# main.net
KiCad netlist of a schematic drawn in EAGLE
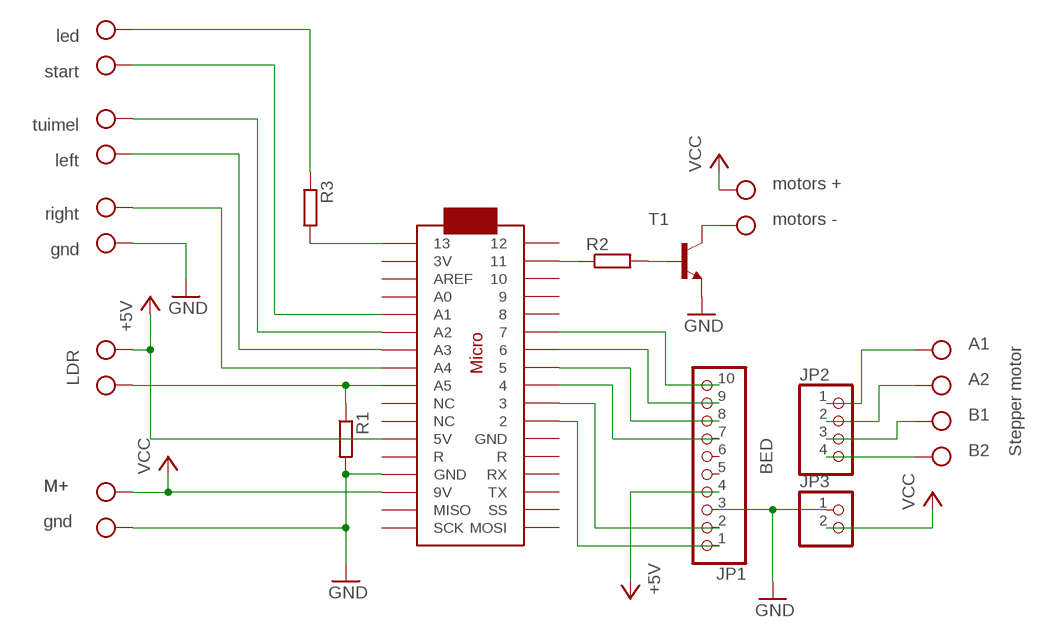
[diagram p0: schematic, sheet 1]

(export (version "E")
  (design (tool "Eeschema 10.0.6"))
  (components
    (comp (ref "JP1")
      (value "PINHD-1X10")
      (footprint "eagle-import:1X10")
      (libsource (lib "eagle-import") (part "PINHD-1X10"))
    )
    (comp (ref "JP2")
      (value "PINHD-1X4")
      (footprint "eagle-import:1X04")
      (libsource (lib "eagle-import") (part "PINHD-1X4"))
    )
    (comp (ref "JP3")
      (value "PINHD-1X2")
      (footprint "eagle-import:1X02")
      (libsource (lib "eagle-import") (part "PINHD-1X2"))
    )
    (comp (ref "R1")
      (value "R-EU_0207/10")
      (footprint "eagle-import:0207_10")
      (libsource (lib "eagle-import") (part "R-EU_0207/10"))
    )
    (comp (ref "R2")
      (value "R-EU_0207/10")
      (footprint "eagle-import:0207_10")
      (libsource (lib "eagle-import") (part "R-EU_0207/10"))
    )
    (comp (ref "R3")
      (value "R-EU_0207/10")
      (footprint "eagle-import:0207_10")
      (libsource (lib "eagle-import") (part "R-EU_0207/10"))
    )
    (comp (ref "T1")
      (value "BD239")
      (footprint "eagle-import:TO220")
      (libsource (lib "eagle-import") (part "BD239"))
    )
    (comp (ref "U$1")
      (value "ARDUINOMICRO")
      (footprint "eagle-import:ARDUINOMICRO")
      (libsource (lib "eagle-import") (part "ARDUINOMICRO"))
    )
    (comp (ref "X1")
      (value "W237-102")
      (footprint "eagle-import:W237-102")
      (fields (field (name "MPN") "237-102"))
      (libsource (lib "eagle-import") (part "W237-102"))
    )
    (comp (ref "X2")
      (value "W237-102")
      (footprint "eagle-import:W237-102")
      (fields (field (name "MPN") "237-102"))
      (libsource (lib "eagle-import") (part "W237-102"))
    )
    (comp (ref "X3")
      (value "W237-102")
      (footprint "eagle-import:W237-102")
      (fields (field (name "MPN") "237-102"))
      (libsource (lib "eagle-import") (part "W237-102"))
    )
    (comp (ref "X4")
      (value "W237-102")
      (footprint "eagle-import:W237-102")
      (fields (field (name "MPN") "237-102"))
      (libsource (lib "eagle-import") (part "W237-102"))
    )
    (comp (ref "X5")
      (value "W237-102")
      (footprint "eagle-import:W237-102")
      (fields (field (name "MPN") "237-102"))
      (libsource (lib "eagle-import") (part "W237-102"))
    )
    (comp (ref "X6")
      (value "W237-102")
      (footprint "eagle-import:W237-102")
      (fields (field (name "MPN") "237-102"))
      (libsource (lib "eagle-import") (part "W237-102"))
    )
    (comp (ref "X7")
      (value "W237-102")
      (footprint "eagle-import:W237-102")
      (fields (field (name "MPN") "237-102"))
      (libsource (lib "eagle-import") (part "W237-102"))
    )
    (comp (ref "X8")
      (value "W237-102")
      (footprint "eagle-import:W237-102")
      (fields (field (name "MPN") "237-102"))
      (libsource (lib "eagle-import") (part "W237-102"))
    )
  )
  (nets
    (net (code "1") (name "+5V") (class "Default")
      (node (ref "JP1") (pin "4") (pinfunction "4_4") (pintype "passive"))
      (node (ref "U$1") (pin "P$23") (pinfunction "5V_P$23") (pintype "bidirectional"))
      (node (ref "X7") (pin "2") (pinfunction "KL_2") (pintype "passive"))
    )
    (net (code "2") (name "GND") (class "Default")
      (node (ref "JP1") (pin "3") (pinfunction "3_3") (pintype "passive"))
      (node (ref "JP3") (pin "1") (pinfunction "1_1") (pintype "passive"))
      (node (ref "R1") (pin "2") (pinfunction "2_2") (pintype "passive"))
      (node (ref "T1") (pin "3") (pinfunction "E_3") (pintype "passive"))
      (node (ref "U$1") (pin "P$12") (pinfunction "GND_P$12") (pintype "bidirectional"))
      (node (ref "X3") (pin "1") (pinfunction "KL_1") (pintype "passive"))
      (node (ref "X6") (pin "2") (pinfunction "KL_2") (pintype "passive"))
    )
    (net (code "3") (name "Net-(T1-B)") (class "Default")
      (node (ref "R2") (pin "2") (pinfunction "2_2") (pintype "passive"))
      (node (ref "T1") (pin "1") (pinfunction "B_1") (pintype "passive"))
    )
    (net (code "4") (name "Net-(T1-C)") (class "Default")
      (node (ref "T1") (pin "2") (pinfunction "C_2") (pintype "passive"))
      (node (ref "X8") (pin "2") (pinfunction "KL_2") (pintype "passive"))
    )
    (net (code "5") (name "Net-(U$1-2)") (class "Default")
      (node (ref "JP1") (pin "1") (pinfunction "1_1") (pintype "passive"))
      (node (ref "U$1") (pin "P$11") (pinfunction "2_P$11") (pintype "bidirectional"))
    )
    (net (code "6") (name "Net-(U$1-3)") (class "Default")
      (node (ref "JP1") (pin "2") (pinfunction "2_2") (pintype "passive"))
      (node (ref "U$1") (pin "P$10") (pinfunction "3_P$10") (pintype "bidirectional"))
    )
    (net (code "7") (name "Net-(U$1-4)") (class "Default")
      (node (ref "JP1") (pin "7") (pinfunction "7_7") (pintype "passive"))
      (node (ref "U$1") (pin "P$9") (pinfunction "4_P$9") (pintype "bidirectional"))
    )
    (net (code "8") (name "Net-(U$1-5)") (class "Default")
      (node (ref "JP1") (pin "8") (pinfunction "8_8") (pintype "passive"))
      (node (ref "U$1") (pin "P$8") (pinfunction "5_P$8") (pintype "bidirectional"))
    )
    (net (code "9") (name "Net-(U$1-6)") (class "Default")
      (node (ref "JP1") (pin "9") (pinfunction "9_9") (pintype "passive"))
      (node (ref "U$1") (pin "P$7") (pinfunction "6_P$7") (pintype "bidirectional"))
    )
    (net (code "10") (name "Net-(U$1-7)") (class "Default")
      (node (ref "JP1") (pin "10") (pinfunction "10_10") (pintype "passive"))
      (node (ref "U$1") (pin "P$6") (pinfunction "7_P$6") (pintype "bidirectional"))
    )
    (net (code "11") (name "Net-(U$1-11)") (class "Default")
      (node (ref "R2") (pin "1") (pinfunction "1_1") (pintype "passive"))
      (node (ref "U$1") (pin "P$2") (pinfunction "11_P$2") (pintype "bidirectional"))
    )
    (net (code "12") (name "Net-(U$1-13)") (class "Default")
      (node (ref "R3") (pin "2") (pinfunction "2_2") (pintype "passive"))
      (node (ref "U$1") (pin "P$34") (pinfunction "13_P$34") (pintype "bidirectional"))
    )
    (net (code "13") (name "Net-(U$1-A1)") (class "Default")
      (node (ref "U$1") (pin "P$30") (pinfunction "A1_P$30") (pintype "bidirectional"))
      (node (ref "X4") (pin "2") (pinfunction "KL_2") (pintype "passive"))
    )
    (net (code "14") (name "Net-(U$1-A2)") (class "Default")
      (node (ref "U$1") (pin "P$29") (pinfunction "A2_P$29") (pintype "bidirectional"))
      (node (ref "X5") (pin "1") (pinfunction "KL_1") (pintype "passive"))
    )
    (net (code "15") (name "Net-(U$1-A3)") (class "Default")
      (node (ref "U$1") (pin "P$28") (pinfunction "A3_P$28") (pintype "bidirectional"))
      (node (ref "X5") (pin "2") (pinfunction "KL_2") (pintype "passive"))
    )
    (net (code "16") (name "Net-(U$1-A4)") (class "Default")
      (node (ref "U$1") (pin "P$27") (pinfunction "A4_P$27") (pintype "bidirectional"))
      (node (ref "X6") (pin "1") (pinfunction "KL_1") (pintype "passive"))
    )
    (net (code "17") (name "Net-(U$1-A5)") (class "Default")
      (node (ref "R1") (pin "1") (pinfunction "1_1") (pintype "passive"))
      (node (ref "U$1") (pin "P$26") (pinfunction "A5_P$26") (pintype "bidirectional"))
      (node (ref "X7") (pin "1") (pinfunction "KL_1") (pintype "passive"))
    )
    (net (code "18") (name "Net-(X1A-KL)") (class "Default")
      (node (ref "JP2") (pin "1") (pinfunction "1_1") (pintype "passive"))
      (node (ref "X1") (pin "1") (pinfunction "KL_1") (pintype "passive"))
    )
    (net (code "19") (name "Net-(X1B-KL)") (class "Default")
      (node (ref "JP2") (pin "2") (pinfunction "2_2") (pintype "passive"))
      (node (ref "X1") (pin "2") (pinfunction "KL_2") (pintype "passive"))
    )
    (net (code "20") (name "Net-(X2A-KL)") (class "Default")
      (node (ref "JP2") (pin "3") (pinfunction "3_3") (pintype "passive"))
      (node (ref "X2") (pin "1") (pinfunction "KL_1") (pintype "passive"))
    )
    (net (code "21") (name "Net-(X2B-KL)") (class "Default")
      (node (ref "JP2") (pin "4") (pinfunction "4_4") (pintype "passive"))
      (node (ref "X2") (pin "2") (pinfunction "KL_2") (pintype "passive"))
    )
    (net (code "22") (name "Net-(X4A-KL)") (class "Default")
      (node (ref "R3") (pin "1") (pinfunction "1_1") (pintype "passive"))
      (node (ref "X4") (pin "1") (pinfunction "KL_1") (pintype "passive"))
    )
    (net (code "23") (name "VCC") (class "Default")
      (node (ref "JP3") (pin "2") (pinfunction "2_2") (pintype "passive"))
      (node (ref "U$1") (pin "P$20") (pinfunction "9V_P$20") (pintype "bidirectional"))
      (node (ref "X3") (pin "2") (pinfunction "KL_2") (pintype "passive"))
      (node (ref "X8") (pin "1") (pinfunction "KL_1") (pintype "passive"))
    )
    (net (code "24") (name "unconnected-(JP1-Pad5)") (class "Default")
      (node (ref "JP1") (pin "5") (pinfunction "5_5") (pintype "passive"))
    )
    (net (code "25") (name "unconnected-(JP1-Pad6)") (class "Default")
      (node (ref "JP1") (pin "6") (pinfunction "6_6") (pintype "passive"))
    )
    (net (code "26") (name "unconnected-(U$1-3V-PadP$33)") (class "Default")
      (node (ref "U$1") (pin "P$33") (pinfunction "3V_P$33") (pintype "bidirectional"))
    )
    (net (code "27") (name "unconnected-(U$1-8-PadP$5)") (class "Default")
      (node (ref "U$1") (pin "P$5") (pinfunction "8_P$5") (pintype "bidirectional"))
    )
    (net (code "28") (name "unconnected-(U$1-9-PadP$4)") (class "Default")
      (node (ref "U$1") (pin "P$4") (pinfunction "9_P$4") (pintype "bidirectional"))
    )
    (net (code "29") (name "unconnected-(U$1-10-PadP$3)") (class "Default")
      (node (ref "U$1") (pin "P$3") (pinfunction "10_P$3") (pintype "bidirectional"))
    )
    (net (code "30") (name "unconnected-(U$1-12-PadP$1)") (class "Default")
      (node (ref "U$1") (pin "P$1") (pinfunction "12_P$1") (pintype "bidirectional"))
    )
    (net (code "31") (name "unconnected-(U$1-A0-PadP$31)") (class "Default")
      (node (ref "U$1") (pin "P$31") (pinfunction "A0_P$31") (pintype "bidirectional"))
    )
    (net (code "32") (name "unconnected-(U$1-AREF-PadP$32)") (class "Default")
      (node (ref "U$1") (pin "P$32") (pinfunction "AREF_P$32") (pintype "bidirectional"))
    )
    (net (code "33") (name "unconnected-(U$1-GND-PadP$21)") (class "Default")
      (node (ref "U$1") (pin "P$21") (pinfunction "GND_P$21") (pintype "bidirectional"))
    )
    (net (code "34") (name "unconnected-(U$1-MISO-PadP$19)") (class "Default")
      (node (ref "U$1") (pin "P$19") (pinfunction "MISO_P$19") (pintype "bidirectional"))
    )
    (net (code "35") (name "unconnected-(U$1-MOSI-PadP$17)") (class "Default")
      (node (ref "U$1") (pin "P$17") (pinfunction "MOSI_P$17") (pintype "bidirectional"))
    )
    (net (code "36") (name "unconnected-(U$1-NC-PadP$24)") (class "Default")
      (node (ref "U$1") (pin "P$24") (pinfunction "NC_P$24") (pintype "bidirectional"))
    )
    (net (code "37") (name "unconnected-(U$1-NC-PadP$25)") (class "Default")
      (node (ref "U$1") (pin "P$25") (pinfunction "NC_P$25") (pintype "bidirectional"))
    )
    (net (code "38") (name "unconnected-(U$1-R-PadP$13)") (class "Default")
      (node (ref "U$1") (pin "P$13") (pinfunction "R_P$13") (pintype "bidirectional"))
    )
    (net (code "39") (name "unconnected-(U$1-R-PadP$22)") (class "Default")
      (node (ref "U$1") (pin "P$22") (pinfunction "R_P$22") (pintype "bidirectional"))
    )
    (net (code "40") (name "unconnected-(U$1-RX-PadP$14)") (class "Default")
      (node (ref "U$1") (pin "P$14") (pinfunction "RX_P$14") (pintype "bidirectional"))
    )
    (net (code "41") (name "unconnected-(U$1-SCK-PadP$18)") (class "Default")
      (node (ref "U$1") (pin "P$18") (pinfunction "SCK_P$18") (pintype "bidirectional"))
    )
    (net (code "42") (name "unconnected-(U$1-SS-PadP$16)") (class "Default")
      (node (ref "U$1") (pin "P$16") (pinfunction "SS_P$16") (pintype "bidirectional"))
    )
    (net (code "43") (name "unconnected-(U$1-TX-PadP$15)") (class "Default")
      (node (ref "U$1") (pin "P$15") (pinfunction "TX_P$15") (pintype "bidirectional"))
    )
  )
)
